# reembox.net
KiCad netlist of a schematic drawn in EAGLE
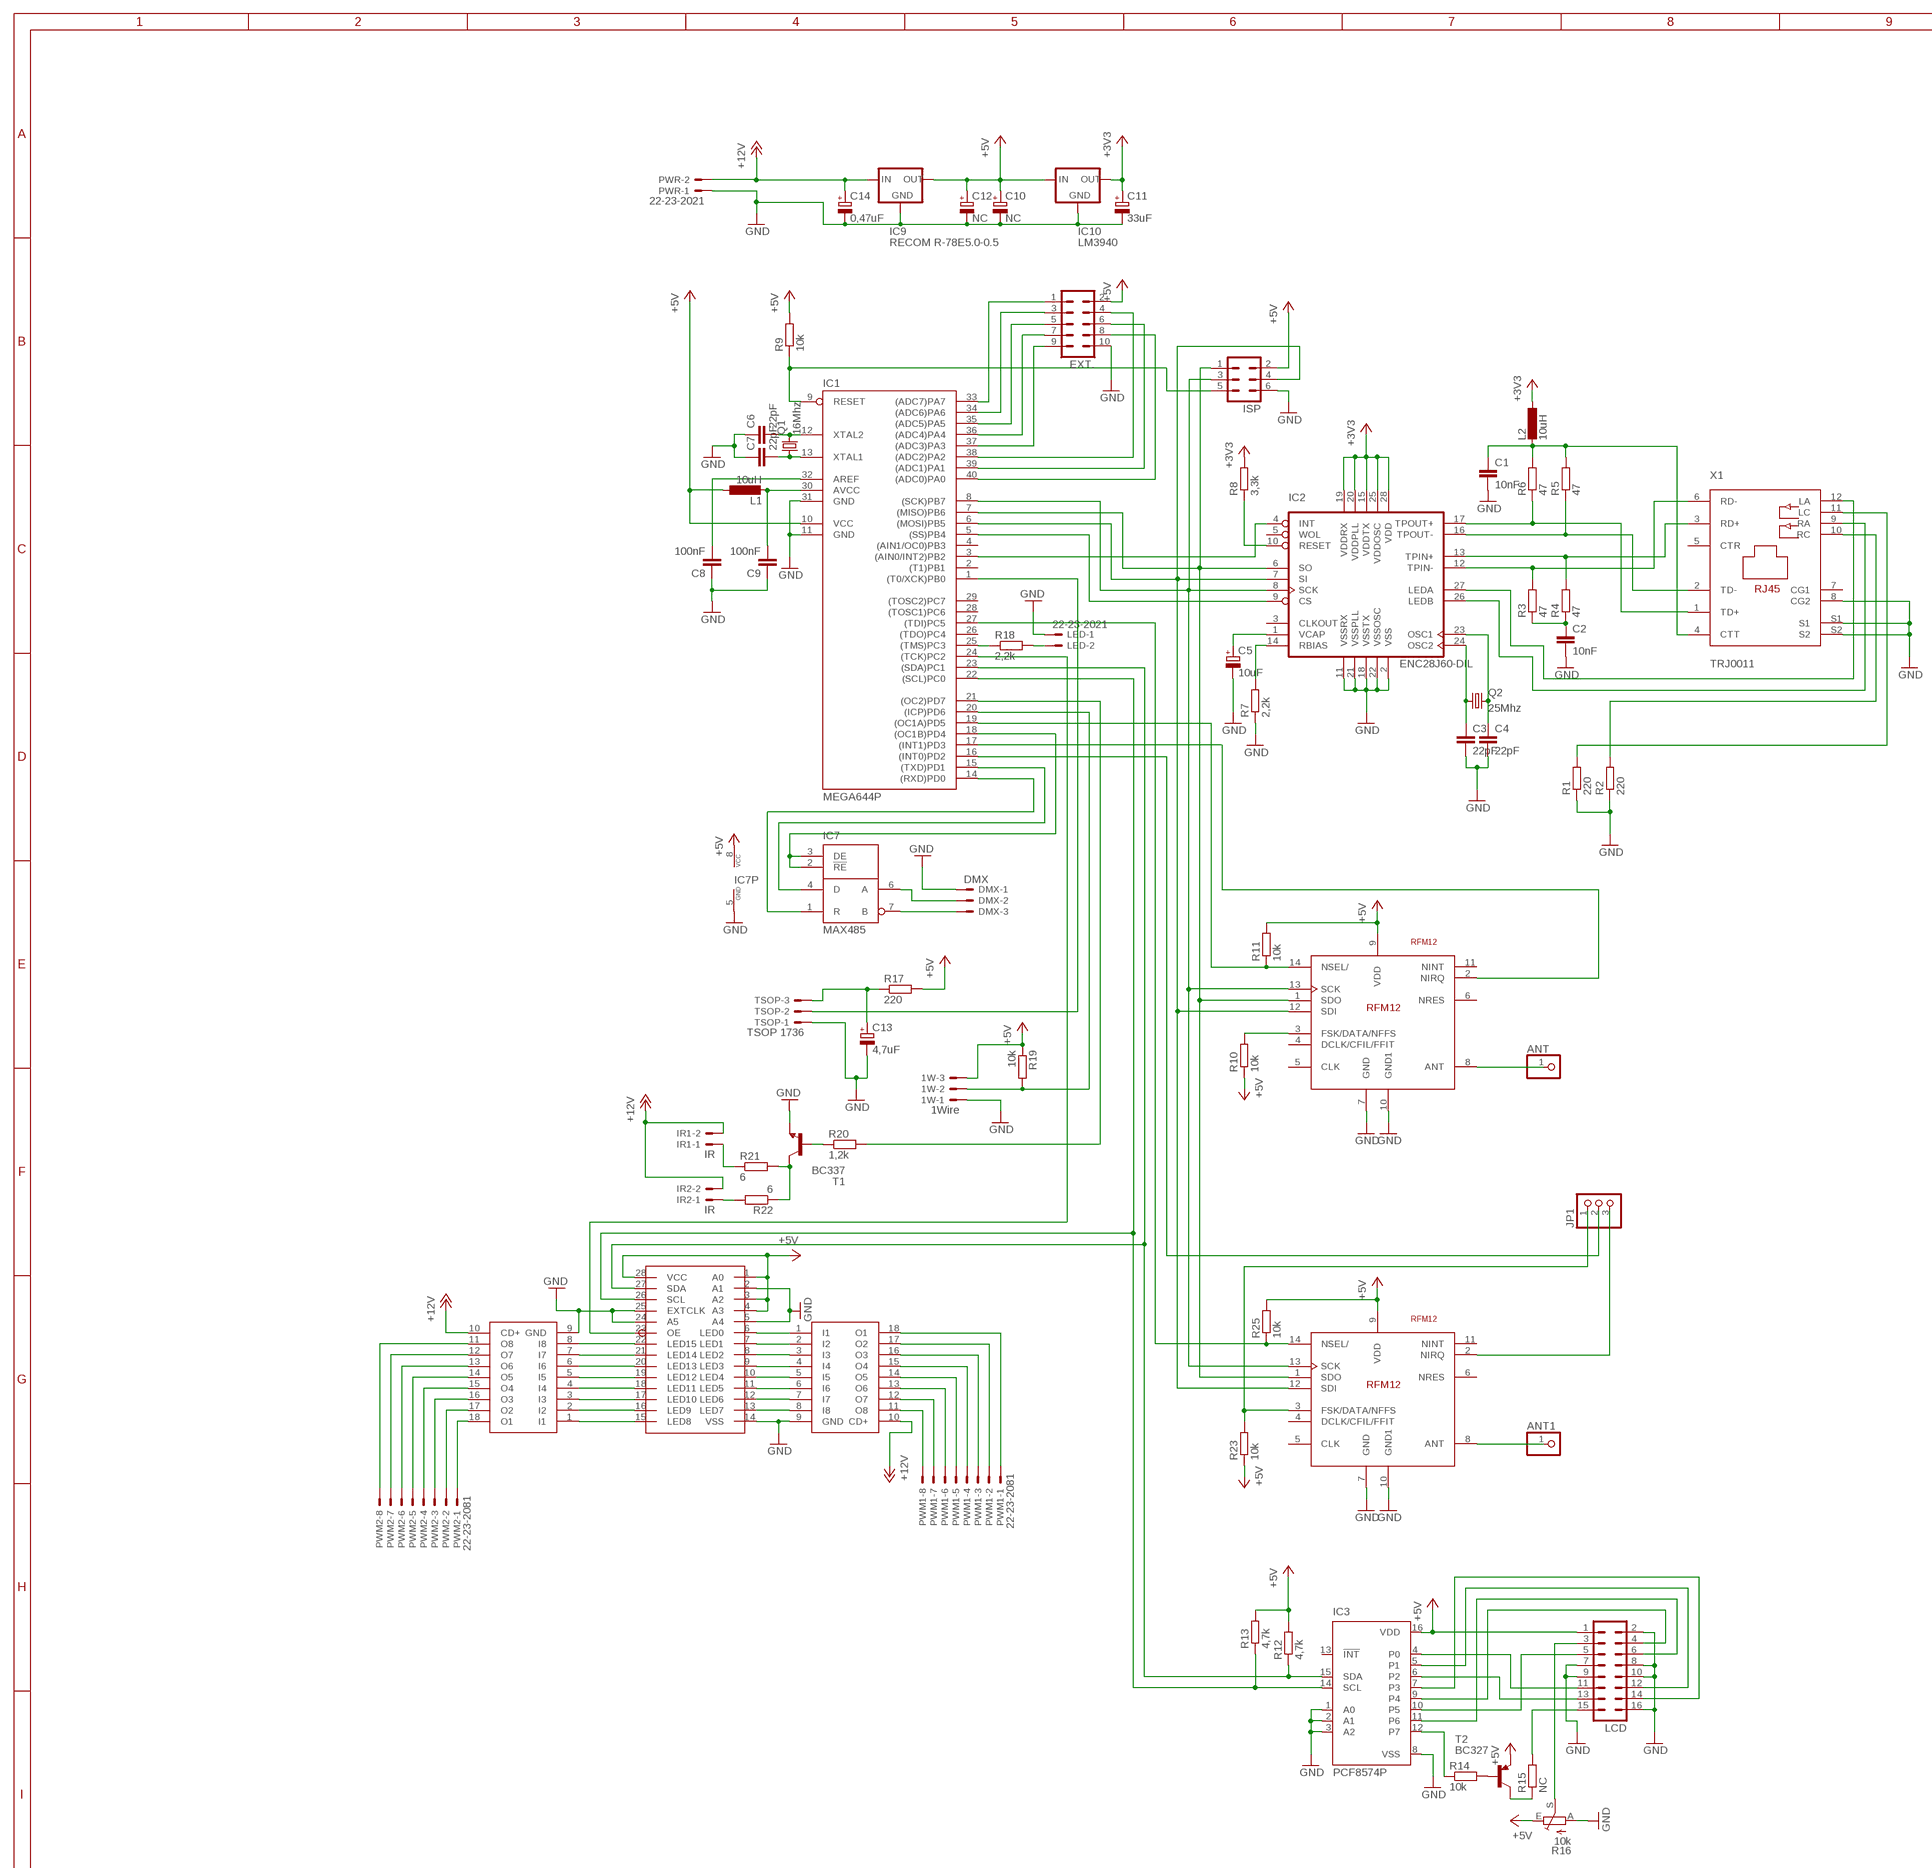
[diagram p0: schematic, sheet 1, part 1 of 2]
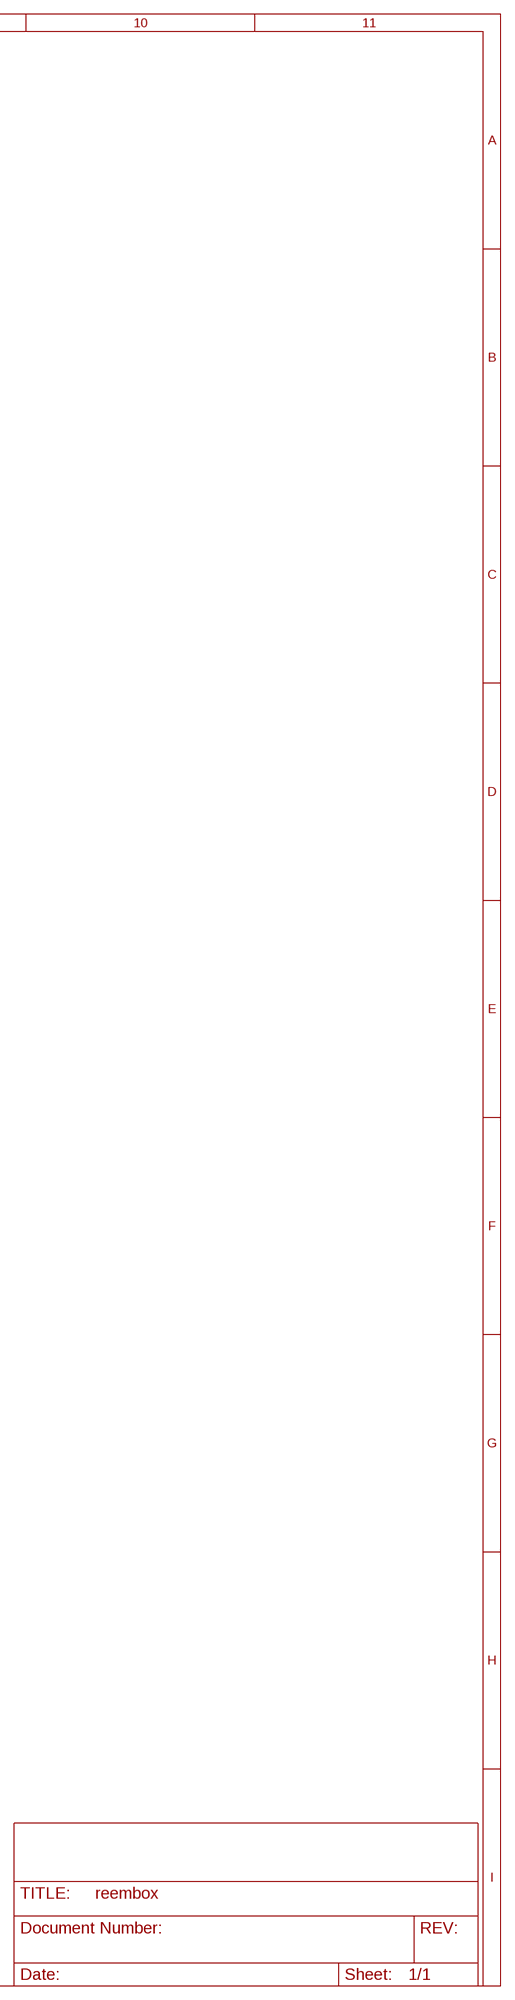
[diagram p1: schematic, sheet 1, part 2 of 2]

(export (version "E")
  (design (tool "Eeschema 10.0.6"))
  (components
    (comp (ref "1W")
      (value "1Wire")
      (footprint "eagle-import:CON-MOLEX_22-23-2031")
      (fields (field (name "MF") "MOLEX") (field (name "MPN") "22-23-2031"))
      (libsource (lib "eagle-import") (part "CON-MOLEX_22-23-2031"))
    )
    (comp (ref "ANT")
      (value "PINHD-1X1")
      (footprint "eagle-import:1X01")
      (libsource (lib "eagle-import") (part "PINHD-1X1"))
    )
    (comp (ref "ANT1")
      (value "PINHD-1X1")
      (footprint "eagle-import:1X01")
      (libsource (lib "eagle-import") (part "PINHD-1X1"))
    )
    (comp (ref "C1")
      (value "10nF")
      (footprint "eagle-import:C050-025X075")
      (libsource (lib "eagle-import") (part "C-EU050-025X075"))
    )
    (comp (ref "C2")
      (value "10nF")
      (footprint "eagle-import:C050-025X075")
      (libsource (lib "eagle-import") (part "C-EU050-025X075"))
    )
    (comp (ref "C3")
      (value "22pF")
      (footprint "eagle-import:C050-024X044")
      (libsource (lib "eagle-import") (part "C-EU050-024X044"))
    )
    (comp (ref "C4")
      (value "22pF")
      (footprint "eagle-import:C050-024X044")
      (libsource (lib "eagle-import") (part "C-EU050-024X044"))
    )
    (comp (ref "C5")
      (value "10uF")
      (footprint "eagle-import:E2,5-6")
      (libsource (lib "eagle-import") (part "CPOL-EUE2.5-6"))
    )
    (comp (ref "C6")
      (value "22pF")
      (footprint "eagle-import:C050-024X044")
      (libsource (lib "eagle-import") (part "C-EU050-024X044"))
    )
    (comp (ref "C7")
      (value "22pF")
      (footprint "eagle-import:C050-024X044")
      (libsource (lib "eagle-import") (part "C-EU050-024X044"))
    )
    (comp (ref "C8")
      (value "100nF")
      (footprint "eagle-import:C050-025X075")
      (libsource (lib "eagle-import") (part "C-EU050-025X075"))
    )
    (comp (ref "C9")
      (value "100nF")
      (footprint "eagle-import:C050-025X075")
      (libsource (lib "eagle-import") (part "C-EU050-025X075"))
    )
    (comp (ref "C10")
      (value "NC")
      (footprint "eagle-import:E2,5-6")
      (libsource (lib "eagle-import") (part "CPOL-EUE2.5-6"))
    )
    (comp (ref "C11")
      (value "33uF")
      (footprint "eagle-import:E2,5-6")
      (libsource (lib "eagle-import") (part "CPOL-EUE2.5-6"))
    )
    (comp (ref "C12")
      (value "NC")
      (footprint "eagle-import:E2,5-6")
      (libsource (lib "eagle-import") (part "CPOL-EUE2.5-6"))
    )
    (comp (ref "C13")
      (value "4,7uF")
      (footprint "eagle-import:E2,5-6E")
      (libsource (lib "eagle-import") (part "CPOL-EUE2,5-6E"))
    )
    (comp (ref "C14")
      (value "0,47uF")
      (footprint "eagle-import:E2,5-6")
      (libsource (lib "eagle-import") (part "CPOL-EUE2.5-6"))
    )
    (comp (ref "DMX")
      (value "DMX")
      (footprint "eagle-import:22-23-2031")
      (fields (field (name "MF") "MOLEX") (field (name "MPN") "22-23-2031"))
      (libsource (lib "eagle-import") (part "22-23-2031"))
    )
    (comp (ref "EXT.")
      (value "ML10L")
      (footprint "eagle-import:ML10L")
      (fields (field (name "OC_FARNELL") "unknown") (field (name "OC_NEWARK") "unknown"))
      (libsource (lib "eagle-import") (part "ML10L"))
    )
    (comp (ref "IC1")
      (value "MEGA644P")
      (footprint "eagle-import:DIL40")
      (fields (field (name "MPN") "ATMEGA32-16PU"))
      (libsource (lib "eagle-import") (part "MEGA32-P"))
    )
    (comp (ref "IC2")
      (value "ENC28J60-DIL")
      (footprint "eagle-import:DIL28-3")
      (libsource (lib "eagle-import") (part "ENC28J60-DIL"))
    )
    (comp (ref "IC3")
      (value "PCF8574P")
      (footprint "eagle-import:DIL16")
      (fields (field (name "MPN") "PCF8574PN"))
      (libsource (lib "eagle-import") (part "PCF8574P"))
    )
    (comp (ref "IC4")
      (value "PCA9685PW")
      (footprint "eagle-import:TSSOP28")
      (libsource (lib "eagle-import") (part "PCA9685PW"))
    )
    (comp (ref "IC5")
      (value "ULN2803")
      (footprint "eagle-import:DIL18")
      (libsource (lib "eagle-import") (part "ULN2803"))
    )
    (comp (ref "IC6")
      (value "ULN2803")
      (footprint "eagle-import:DIL18")
      (libsource (lib "eagle-import") (part "ULN2803"))
    )
    (comp (ref "IC7")
      (value "MAX485")
      (footprint "eagle-import:DIL08")
      (fields (field (name "MF") "TEXAS INSTRUMENTS") (field (name "MPN") "SN75ALS176P"))
      (libsource (lib "eagle-import") (part "75ALS176P"))
    )
    (comp (ref "IC8")
      (value "RFM12")
      (footprint "eagle-import:RFM12")
      (libsource (lib "eagle-import") (part "FRM12"))
    )
    (comp (ref "IC9")
      (value "RECOM R-78E5.0-0.5")
      (footprint "eagle-import:78XXS")
      (libsource (lib "eagle-import") (part "78XXS"))
    )
    (comp (ref "IC10")
      (value "LM3940")
      (footprint "eagle-import:78XXS")
      (libsource (lib "eagle-import") (part "78XXS"))
    )
    (comp (ref "IC11")
      (value "RFM12")
      (footprint "eagle-import:RFM12")
      (libsource (lib "eagle-import") (part "FRM12"))
    )
    (comp (ref "IR1")
      (value "IR")
      (footprint "eagle-import:22-23-2021")
      (fields (field (name "MF") "MOLEX") (field (name "MPN") "22-23-2021"))
      (libsource (lib "eagle-import") (part "22-23-2021"))
    )
    (comp (ref "IR2")
      (value "IR")
      (footprint "eagle-import:22-23-2021")
      (fields
        (field (name "MF") "MOLEX")
        (field (name "MPN") "22-23-2021")
        (field (name "MF_1") "MOLEX")
        (field (name "MPN_1") "22-23-2021")
        (field (name "OC_FARNELL") "1462926")
        (field (name "OC_NEWARK") "25C3832")
      )
      (libsource (lib "eagle-import") (part "22-23-2021"))
    )
    (comp (ref "ISP")
      (value "ML6")
      (footprint "eagle-import:ML6")
      (libsource (lib "eagle-import") (part "ML6"))
    )
    (comp (ref "JP1")
      (value "PINHD-1X3")
      (footprint "eagle-import:1X03")
      (libsource (lib "eagle-import") (part "PINHD-1X3"))
    )
    (comp (ref "L1")
      (value "10uH")
      (footprint "eagle-import:0207_2V")
      (libsource (lib "eagle-import") (part "L-EU0207/2V"))
    )
    (comp (ref "L2")
      (value "10uH")
      (footprint "eagle-import:0207_2V")
      (libsource (lib "eagle-import") (part "L-EU0207/2V"))
    )
    (comp (ref "LCD")
      (value "ML16")
      (footprint "eagle-import:ML16")
      (libsource (lib "eagle-import") (part "ML16"))
    )
    (comp (ref "LED")
      (value "22-23-2021")
      (footprint "eagle-import:22-23-2021")
      (fields
        (field (name "MF") "MOLEX")
        (field (name "MF_1") "MOLEX")
        (field (name "MPN") "22-23-2021")
        (field (name "OC_FARNELL") "1462926")
        (field (name "OC_NEWARK") "25C3832")
      )
      (libsource (lib "eagle-import") (part "22-23-2021"))
    )
    (comp (ref "PWM1")
      (value "22-23-2081")
      (footprint "eagle-import:22-23-2081")
      (fields (field (name "MF") "MOLEX"))
      (libsource (lib "eagle-import") (part "22-23-2081"))
    )
    (comp (ref "PWM2")
      (value "22-23-2081")
      (footprint "eagle-import:22-23-2081")
      (fields (field (name "MF") "MOLEX"))
      (libsource (lib "eagle-import") (part "22-23-2081"))
    )
    (comp (ref "PWR")
      (value "22-23-2021")
      (footprint "eagle-import:22-23-2021")
      (fields (field (name "MF") "MOLEX"))
      (libsource (lib "eagle-import") (part "22-23-2021"))
    )
    (comp (ref "Q1")
      (value "16Mhz")
      (footprint "eagle-import:HC49U-V")
      (libsource (lib "eagle-import") (part "CRYSTALHC49U-V"))
    )
    (comp (ref "Q2")
      (value "25Mhz")
      (footprint "eagle-import:HC49U-V")
      (libsource (lib "eagle-import") (part "CRYSTALHC49U-V"))
    )
    (comp (ref "R1")
      (value "220")
      (footprint "eagle-import:0207_2V")
      (libsource (lib "eagle-import") (part "R-EU_0207/2V"))
    )
    (comp (ref "R2")
      (value "220")
      (footprint "eagle-import:0207_2V")
      (libsource (lib "eagle-import") (part "R-EU_0207/2V"))
    )
    (comp (ref "R3")
      (value "47")
      (footprint "eagle-import:0207_2V")
      (libsource (lib "eagle-import") (part "R-EU_0207/2V"))
    )
    (comp (ref "R4")
      (value "47")
      (footprint "eagle-import:0207_2V")
      (libsource (lib "eagle-import") (part "R-EU_0207/2V"))
    )
    (comp (ref "R5")
      (value "47")
      (footprint "eagle-import:0207_2V")
      (libsource (lib "eagle-import") (part "R-EU_0207/2V"))
    )
    (comp (ref "R6")
      (value "47")
      (footprint "eagle-import:0207_2V")
      (libsource (lib "eagle-import") (part "R-EU_0207/2V"))
    )
    (comp (ref "R7")
      (value "2,2k")
      (footprint "eagle-import:0207_7")
      (libsource (lib "eagle-import") (part "resistor_R-EU_0207/7"))
    )
    (comp (ref "R8")
      (value "3,3k")
      (footprint "eagle-import:0207_10")
      (libsource (lib "eagle-import") (part "R-EU_0207/10"))
    )
    (comp (ref "R9")
      (value "10k")
      (footprint "eagle-import:0207_2V")
      (libsource (lib "eagle-import") (part "R-EU_0207/2V"))
    )
    (comp (ref "R10")
      (value "10k")
      (footprint "eagle-import:0207_10")
      (libsource (lib "eagle-import") (part "R-EU_0207/10"))
    )
    (comp (ref "R11")
      (value "10k")
      (footprint "eagle-import:0207_10")
      (libsource (lib "eagle-import") (part "R-EU_0207/10"))
    )
    (comp (ref "R12")
      (value "4,7k")
      (footprint "eagle-import:0207_10")
      (libsource (lib "eagle-import") (part "R-EU_0207/10"))
    )
    (comp (ref "R13")
      (value "4,7k")
      (footprint "eagle-import:0207_10")
      (libsource (lib "eagle-import") (part "R-EU_0207/10"))
    )
    (comp (ref "R14")
      (value "10k")
      (footprint "eagle-import:0207_10")
      (libsource (lib "eagle-import") (part "R-EU_0207/10"))
    )
    (comp (ref "R15")
      (value "NC")
      (footprint "eagle-import:0207_10")
      (libsource (lib "eagle-import") (part "R-EU_0207/10"))
    )
    (comp (ref "R16")
      (value "10k")
      (footprint "eagle-import:PT-10S")
      (libsource (lib "eagle-import") (part "TRIM_EU-PT10S"))
    )
    (comp (ref "R17")
      (value "220")
      (footprint "eagle-import:0207_2V")
      (libsource (lib "eagle-import") (part "R-EU_0207/2V"))
    )
    (comp (ref "R18")
      (value "2,2k")
      (footprint "eagle-import:0207_2V")
      (libsource (lib "eagle-import") (part "R-EU_0207/2V"))
    )
    (comp (ref "R19")
      (value "10k")
      (footprint "eagle-import:0207_10")
      (libsource (lib "eagle-import") (part "R-EU_0207/10"))
    )
    (comp (ref "R20")
      (value "1,2k")
      (footprint "eagle-import:RCL_0207_2V")
      (libsource (lib "eagle-import") (part "RCL_R-EU_0207/2V"))
    )
    (comp (ref "R21")
      (value "6")
      (footprint "eagle-import:RCL_0207_2V")
      (libsource (lib "eagle-import") (part "RCL_R-EU_0207/2V"))
    )
    (comp (ref "R22")
      (value "6")
      (footprint "eagle-import:RCL_0207_2V")
      (libsource (lib "eagle-import") (part "RCL_R-EU_0207/2V"))
    )
    (comp (ref "R23")
      (value "10k")
      (footprint "eagle-import:0207_10")
      (libsource (lib "eagle-import") (part "R-EU_0207/10"))
    )
    (comp (ref "R25")
      (value "10k")
      (footprint "eagle-import:0207_2V")
      (libsource (lib "eagle-import") (part "R-EU_0207/2V"))
    )
    (comp (ref "T1")
      (value "BC337")
      (footprint "eagle-import:TO92")
      (libsource (lib "eagle-import") (part "BC337"))
    )
    (comp (ref "T2")
      (value "BC327")
      (footprint "eagle-import:TO92")
      (libsource (lib "eagle-import") (part "BC327"))
    )
    (comp (ref "TSOP")
      (value "TSOP 1736")
      (footprint "eagle-import:22-23-2031")
      (fields (field (name "MF") "MOLEX") (field (name "MPN") "22-23-2031"))
      (libsource (lib "eagle-import") (part "22-23-2031"))
    )
    (comp (ref "X1")
      (value "TRJ0011")
      (footprint "eagle-import:TRJ0011")
      (libsource (lib "eagle-import") (part "TRJ0011"))
    )
  )
  (nets
    (net (code "1") (name "+3V3") (class "Default")
      (node (ref "C11") (pin "+") (pinfunction "+_+") (pintype "passive"))
      (node (ref "IC10") (pin "OUT") (pinfunction "OUT_OUT") (pintype "passive"))
      (node (ref "IC2") (pin "15") (pinfunction "VDDTX_15") (pintype "power_in"))
      (node (ref "IC2") (pin "19") (pinfunction "VDDRX_19") (pintype "power_in"))
      (node (ref "IC2") (pin "20") (pinfunction "VDDPLL_20") (pintype "power_in"))
      (node (ref "IC2") (pin "25") (pinfunction "VDDOSC_25") (pintype "power_in"))
      (node (ref "IC2") (pin "28") (pinfunction "VDD_28") (pintype "power_in"))
      (node (ref "L2") (pin "1") (pinfunction "1_1") (pintype "passive"))
      (node (ref "R8") (pin "2") (pinfunction "2_2") (pintype "passive"))
    )
    (net (code "2") (name "+5V") (class "Default")
      (node (ref "1W") (pin "3") (pinfunction "S_3") (pintype "passive"))
      (node (ref "C10") (pin "+") (pinfunction "+_+") (pintype "passive"))
      (node (ref "C12") (pin "+") (pinfunction "+_+") (pintype "passive"))
      (node (ref "EXT.") (pin "2") (pinfunction "2_2") (pintype "passive"))
      (node (ref "IC1") (pin "10") (pinfunction "VCC_10") (pintype "power_in"))
      (node (ref "IC10") (pin "IN") (pinfunction "IN_IN") (pintype "input"))
      (node (ref "IC11") (pin "9") (pinfunction "VDD_9") (pintype "power_in"))
      (node (ref "IC3") (pin "16") (pinfunction "VDD_16") (pintype "power_in"))
      (node (ref "IC4") (pin "1") (pinfunction "A0_1") (pintype "bidirectional"))
      (node (ref "IC4") (pin "28") (pinfunction "VCC_28") (pintype "bidirectional"))
      (node (ref "IC4") (pin "3") (pinfunction "A2_3") (pintype "bidirectional"))
      (node (ref "IC4") (pin "4") (pinfunction "A3_4") (pintype "bidirectional"))
      (node (ref "IC7") (pin "8") (pinfunction "VCC_8") (pintype "power_in"))
      (node (ref "IC8") (pin "9") (pinfunction "VDD_9") (pintype "power_in"))
      (node (ref "IC9") (pin "OUT") (pinfunction "OUT_OUT") (pintype "passive"))
      (node (ref "ISP") (pin "2") (pinfunction "2_2") (pintype "passive"))
      (node (ref "L1") (pin "1") (pinfunction "1_1") (pintype "passive"))
      (node (ref "LCD") (pin "1") (pinfunction "1_1") (pintype "passive"))
      (node (ref "R10") (pin "1") (pinfunction "1_1") (pintype "passive"))
      (node (ref "R11") (pin "2") (pinfunction "2_2") (pintype "passive"))
      (node (ref "R12") (pin "2") (pinfunction "2_2") (pintype "passive"))
      (node (ref "R13") (pin "2") (pinfunction "2_2") (pintype "passive"))
      (node (ref "R16") (pin "E") (pinfunction "E_E") (pintype "passive"))
      (node (ref "R17") (pin "2") (pinfunction "2_2") (pintype "passive"))
      (node (ref "R19") (pin "1") (pinfunction "1_1") (pintype "passive"))
      (node (ref "R23") (pin "1") (pinfunction "1_1") (pintype "passive"))
      (node (ref "R25") (pin "2") (pinfunction "2_2") (pintype "passive"))
      (node (ref "R9") (pin "2") (pinfunction "2_2") (pintype "passive"))
      (node (ref "T2") (pin "1") (pinfunction "E_1") (pintype "passive"))
    )
    (net (code "3") (name "+12V") (class "Default")
      (node (ref "C14") (pin "+") (pinfunction "+_+") (pintype "passive"))
      (node (ref "IC5") (pin "10") (pinfunction "CD+_10") (pintype "bidirectional"))
      (node (ref "IC6") (pin "10") (pinfunction "CD+_10") (pintype "bidirectional"))
      (node (ref "IC9") (pin "IN") (pinfunction "IN_IN") (pintype "input"))
      (node (ref "IR1") (pin "2") (pinfunction "S_2") (pintype "passive"))
      (node (ref "IR2") (pin "2") (pinfunction "S_2") (pintype "passive"))
      (node (ref "PWR") (pin "2") (pinfunction "S_2") (pintype "passive"))
    )
    (net (code "4") (name "GND") (class "Default")
      (node (ref "1W") (pin "1") (pinfunction "S_1") (pintype "passive"))
      (node (ref "C1") (pin "2") (pinfunction "2_2") (pintype "passive"))
      (node (ref "C10") (pin "-") (pinfunction "-_-") (pintype "passive"))
      (node (ref "C11") (pin "-") (pinfunction "-_-") (pintype "passive"))
      (node (ref "C12") (pin "-") (pinfunction "-_-") (pintype "passive"))
      (node (ref "C13") (pin "-") (pinfunction "-_-") (pintype "passive"))
      (node (ref "C14") (pin "-") (pinfunction "-_-") (pintype "passive"))
      (node (ref "C2") (pin "2") (pinfunction "2_2") (pintype "passive"))
      (node (ref "C3") (pin "2") (pinfunction "2_2") (pintype "passive"))
      (node (ref "C4") (pin "2") (pinfunction "2_2") (pintype "passive"))
      (node (ref "C5") (pin "-") (pinfunction "-_-") (pintype "passive"))
      (node (ref "C6") (pin "1") (pinfunction "1_1") (pintype "passive"))
      (node (ref "C7") (pin "1") (pinfunction "1_1") (pintype "passive"))
      (node (ref "C8") (pin "1") (pinfunction "1_1") (pintype "passive"))
      (node (ref "C9") (pin "1") (pinfunction "1_1") (pintype "passive"))
      (node (ref "DMX") (pin "1") (pinfunction "S_1") (pintype "passive"))
      (node (ref "EXT.") (pin "10") (pinfunction "10_10") (pintype "passive"))
      (node (ref "IC1") (pin "11") (pinfunction "GND_11") (pintype "power_in"))
      (node (ref "IC1") (pin "31") (pinfunction "GND_31") (pintype "power_in"))
      (node (ref "IC10") (pin "GND") (pinfunction "GND_GND") (pintype "input"))
      (node (ref "IC11") (pin "10") (pinfunction "GND1_10") (pintype "passive"))
      (node (ref "IC11") (pin "7") (pinfunction "GND_7") (pintype "passive"))
      (node (ref "IC2") (pin "11") (pinfunction "VSSRX_11") (pintype "power_in"))
      (node (ref "IC2") (pin "18") (pinfunction "VSSTX_18") (pintype "power_in"))
      (node (ref "IC2") (pin "2") (pinfunction "VSS_2") (pintype "power_in"))
      (node (ref "IC2") (pin "21") (pinfunction "VSSPLL_21") (pintype "power_in"))
      (node (ref "IC2") (pin "22") (pinfunction "VSSOSC_22") (pintype "power_in"))
      (node (ref "IC3") (pin "1") (pinfunction "A0_1") (pintype "input"))
      (node (ref "IC3") (pin "2") (pinfunction "A1_2") (pintype "input"))
      (node (ref "IC3") (pin "3") (pinfunction "A2_3") (pintype "input"))
      (node (ref "IC3") (pin "8") (pinfunction "VSS_8") (pintype "power_in"))
      (node (ref "IC4") (pin "14") (pinfunction "VSS_14") (pintype "bidirectional"))
      (node (ref "IC4") (pin "2") (pinfunction "A1_2") (pintype "bidirectional"))
      (node (ref "IC4") (pin "24") (pinfunction "A5_24") (pintype "bidirectional"))
      (node (ref "IC4") (pin "25") (pinfunction "EXTCLK_25") (pintype "bidirectional"))
      (node (ref "IC4") (pin "5") (pinfunction "A4_5") (pintype "bidirectional"))
      (node (ref "IC5") (pin "9") (pinfunction "GND_9") (pintype "bidirectional"))
      (node (ref "IC6") (pin "9") (pinfunction "GND_9") (pintype "bidirectional"))
      (node (ref "IC7") (pin "5") (pinfunction "GND_5") (pintype "power_in"))
      (node (ref "IC8") (pin "10") (pinfunction "GND1_10") (pintype "passive"))
      (node (ref "IC8") (pin "7") (pinfunction "GND_7") (pintype "passive"))
      (node (ref "IC9") (pin "GND") (pinfunction "GND_GND") (pintype "input"))
      (node (ref "ISP") (pin "6") (pinfunction "6_6") (pintype "passive"))
      (node (ref "LCD") (pin "10") (pinfunction "10_10") (pintype "passive"))
      (node (ref "LCD") (pin "16") (pinfunction "16_16") (pintype "passive"))
      (node (ref "LCD") (pin "2") (pinfunction "2_2") (pintype "passive"))
      (node (ref "LCD") (pin "7") (pinfunction "7_7") (pintype "passive"))
      (node (ref "LCD") (pin "8") (pinfunction "8_8") (pintype "passive"))
      (node (ref "LCD") (pin "9") (pinfunction "9_9") (pintype "passive"))
      (node (ref "LED") (pin "1") (pinfunction "S_1") (pintype "passive"))
      (node (ref "PWR") (pin "1") (pinfunction "S_1") (pintype "passive"))
      (node (ref "R1") (pin "1") (pinfunction "1_1") (pintype "passive"))
      (node (ref "R16") (pin "A") (pinfunction "A_A") (pintype "passive"))
      (node (ref "R2") (pin "1") (pinfunction "1_1") (pintype "passive"))
      (node (ref "R7") (pin "1") (pinfunction "1_1") (pintype "passive"))
      (node (ref "T1") (pin "1") (pinfunction "E_1") (pintype "passive"))
      (node (ref "TSOP") (pin "1") (pinfunction "S_1") (pintype "passive"))
      (node (ref "X1") (pin "8") (pinfunction "CG2_8") (pintype "passive"))
      (node (ref "X1") (pin "S1") (pinfunction "S1_S1") (pintype "passive"))
      (node (ref "X1") (pin "S2") (pinfunction "S2_S2") (pintype "passive"))
    )
    (net (code "5") (name "Net-(1WB-S)") (class "Default")
      (node (ref "1W") (pin "2") (pinfunction "S_2") (pintype "passive"))
      (node (ref "IC1") (pin "20") (pinfunction "(ICP)PD6_20") (pintype "bidirectional"))
      (node (ref "R19") (pin "2") (pinfunction "2_2") (pintype "passive"))
    )
    (net (code "6") (name "Net-(C2-Pad1)") (class "Default")
      (node (ref "C2") (pin "1") (pinfunction "1_1") (pintype "passive"))
      (node (ref "R3") (pin "1") (pinfunction "1_1") (pintype "passive"))
      (node (ref "R4") (pin "1") (pinfunction "1_1") (pintype "passive"))
    )
    (net (code "7") (name "Net-(DMXB-S)") (class "Default")
      (node (ref "DMX") (pin "2") (pinfunction "S_2") (pintype "passive"))
      (node (ref "IC7") (pin "6") (pinfunction "A_6") (pintype "bidirectional"))
    )
    (net (code "8") (name "Net-(DMXC-S)") (class "Default")
      (node (ref "DMX") (pin "3") (pinfunction "S_3") (pintype "passive"))
      (node (ref "IC7") (pin "7") (pinfunction "B_7") (pintype "bidirectional"))
    )
    (net (code "9") (name "Net-(IC1-(ADC0)PA0)") (class "Default")
      (node (ref "EXT.") (pin "8") (pinfunction "8_8") (pintype "passive"))
      (node (ref "IC1") (pin "40") (pinfunction "(ADC0)PA0_40") (pintype "bidirectional"))
    )
    (net (code "10") (name "Net-(IC1-(ADC1)PA1)") (class "Default")
      (node (ref "EXT.") (pin "6") (pinfunction "6_6") (pintype "passive"))
      (node (ref "IC1") (pin "39") (pinfunction "(ADC1)PA1_39") (pintype "bidirectional"))
    )
    (net (code "11") (name "Net-(IC1-(ADC2)PA2)") (class "Default")
      (node (ref "EXT.") (pin "4") (pinfunction "4_4") (pintype "passive"))
      (node (ref "IC1") (pin "38") (pinfunction "(ADC2)PA2_38") (pintype "bidirectional"))
    )
    (net (code "12") (name "Net-(IC1-(ADC3)PA3)") (class "Default")
      (node (ref "EXT.") (pin "9") (pinfunction "9_9") (pintype "passive"))
      (node (ref "IC1") (pin "37") (pinfunction "(ADC3)PA3_37") (pintype "bidirectional"))
    )
    (net (code "13") (name "Net-(IC1-(ADC4)PA4)") (class "Default")
      (node (ref "EXT.") (pin "7") (pinfunction "7_7") (pintype "passive"))
      (node (ref "IC1") (pin "36") (pinfunction "(ADC4)PA4_36") (pintype "bidirectional"))
    )
    (net (code "14") (name "Net-(IC1-(ADC5)PA5)") (class "Default")
      (node (ref "EXT.") (pin "5") (pinfunction "5_5") (pintype "passive"))
      (node (ref "IC1") (pin "35") (pinfunction "(ADC5)PA5_35") (pintype "bidirectional"))
    )
    (net (code "15") (name "Net-(IC1-(ADC6)PA6)") (class "Default")
      (node (ref "EXT.") (pin "3") (pinfunction "3_3") (pintype "passive"))
      (node (ref "IC1") (pin "34") (pinfunction "(ADC6)PA6_34") (pintype "bidirectional"))
    )
    (net (code "16") (name "Net-(IC1-(ADC7)PA7)") (class "Default")
      (node (ref "EXT.") (pin "1") (pinfunction "1_1") (pintype "passive"))
      (node (ref "IC1") (pin "33") (pinfunction "(ADC7)PA7_33") (pintype "bidirectional"))
    )
    (net (code "17") (name "Net-(IC1-(AIN0{slash}INT2)PB2)") (class "Default")
      (node (ref "IC1") (pin "3") (pinfunction "(AIN0/INT2)PB2_3") (pintype "bidirectional"))
      (node (ref "IC2") (pin "4") (pinfunction "INT_4") (pintype "output"))
    )
    (net (code "18") (name "Net-(IC1-(INT0)PD2)") (class "Default")
      (node (ref "IC1") (pin "16") (pinfunction "(INT0)PD2_16") (pintype "bidirectional"))
      (node (ref "JP1") (pin "2") (pinfunction "2_2") (pintype "passive"))
    )
    (net (code "19") (name "Net-(IC1-(INT1)PD3)") (class "Default")
      (node (ref "IC1") (pin "17") (pinfunction "(INT1)PD3_17") (pintype "bidirectional"))
      (node (ref "IC8") (pin "2") (pinfunction "NIRQ_2") (pintype "output"))
    )
    (net (code "20") (name "Net-(IC1-(MISO)PB6)") (class "Default")
      (node (ref "IC1") (pin "7") (pinfunction "(MISO)PB6_7") (pintype "bidirectional"))
      (node (ref "IC11") (pin "1") (pinfunction "SDO_1") (pintype "output"))
      (node (ref "IC2") (pin "6") (pinfunction "SO_6") (pintype "open_collector"))
      (node (ref "IC8") (pin "1") (pinfunction "SDO_1") (pintype "output"))
      (node (ref "ISP") (pin "1") (pinfunction "1_1") (pintype "passive"))
    )
    (net (code "21") (name "Net-(IC1-(MOSI)PB5)") (class "Default")
      (node (ref "IC1") (pin "6") (pinfunction "(MOSI)PB5_6") (pintype "bidirectional"))
      (node (ref "IC11") (pin "12") (pinfunction "SDI_12") (pintype "input"))
      (node (ref "IC2") (pin "7") (pinfunction "SI_7") (pintype "input"))
      (node (ref "IC8") (pin "12") (pinfunction "SDI_12") (pintype "input"))
      (node (ref "ISP") (pin "4") (pinfunction "4_4") (pintype "passive"))
    )
    (net (code "22") (name "Net-(IC1-(OC1A)PD5)") (class "Default")
      (node (ref "IC1") (pin "19") (pinfunction "(OC1A)PD5_19") (pintype "bidirectional"))
      (node (ref "IC8") (pin "14") (pinfunction "NSEL/_14") (pintype "input"))
      (node (ref "R11") (pin "1") (pinfunction "1_1") (pintype "passive"))
    )
    (net (code "23") (name "Net-(IC1-(OC1B)PD4)") (class "Default")
      (node (ref "IC1") (pin "18") (pinfunction "(OC1B)PD4_18") (pintype "bidirectional"))
      (node (ref "IC7") (pin "2") (pinfunction "~{RE}_2") (pintype "input"))
      (node (ref "IC7") (pin "3") (pinfunction "DE_3") (pintype "input"))
    )
    (net (code "24") (name "Net-(IC1-(OC2)PD7)") (class "Default")
      (node (ref "IC1") (pin "21") (pinfunction "(OC2)PD7_21") (pintype "bidirectional"))
      (node (ref "R20") (pin "2") (pinfunction "2_2") (pintype "passive"))
    )
    (net (code "25") (name "Net-(IC1-(RXD)PD0)") (class "Default")
      (node (ref "IC1") (pin "14") (pinfunction "(RXD)PD0_14") (pintype "bidirectional"))
      (node (ref "IC7") (pin "1") (pinfunction "R_1") (pintype "output"))
    )
    (net (code "26") (name "Net-(IC1-(SCK)PB7)") (class "Default")
      (node (ref "IC1") (pin "8") (pinfunction "(SCK)PB7_8") (pintype "bidirectional"))
      (node (ref "IC11") (pin "13") (pinfunction "SCK_13") (pintype "input"))
      (node (ref "IC2") (pin "8") (pinfunction "SCK_8") (pintype "input"))
      (node (ref "IC8") (pin "13") (pinfunction "SCK_13") (pintype "input"))
      (node (ref "ISP") (pin "3") (pinfunction "3_3") (pintype "passive"))
    )
    (net (code "27") (name "Net-(IC1-(SCL)PC0)") (class "Default")
      (node (ref "IC1") (pin "22") (pinfunction "(SCL)PC0_22") (pintype "bidirectional"))
      (node (ref "IC3") (pin "14") (pinfunction "SCL_14") (pintype "input"))
      (node (ref "IC4") (pin "26") (pinfunction "SCL_26") (pintype "bidirectional"))
      (node (ref "R13") (pin "1") (pinfunction "1_1") (pintype "passive"))
    )
    (net (code "28") (name "Net-(IC1-(SDA)PC1)") (class "Default")
      (node (ref "IC1") (pin "23") (pinfunction "(SDA)PC1_23") (pintype "bidirectional"))
      (node (ref "IC3") (pin "15") (pinfunction "SDA_15") (pintype "bidirectional"))
      (node (ref "IC4") (pin "27") (pinfunction "SDA_27") (pintype "bidirectional"))
      (node (ref "R12") (pin "1") (pinfunction "1_1") (pintype "passive"))
    )
    (net (code "29") (name "Net-(IC1-(SS)PB4)") (class "Default")
      (node (ref "IC1") (pin "5") (pinfunction "(SS)PB4_5") (pintype "bidirectional"))
      (node (ref "IC2") (pin "9") (pinfunction "CS_9") (pintype "input"))
    )
    (net (code "30") (name "Net-(IC1-(T0{slash}XCK)PB0)") (class "Default")
      (node (ref "IC1") (pin "1") (pinfunction "(T0/XCK)PB0_1") (pintype "bidirectional"))
      (node (ref "TSOP") (pin "2") (pinfunction "S_2") (pintype "passive"))
    )
    (net (code "31") (name "Net-(IC1-(TCK)PC2)") (class "Default")
      (node (ref "IC1") (pin "24") (pinfunction "(TCK)PC2_24") (pintype "bidirectional"))
      (node (ref "IC4") (pin "23") (pinfunction "OE_23") (pintype "bidirectional"))
    )
    (net (code "32") (name "Net-(IC1-(TDI)PC5)") (class "Default")
      (node (ref "IC1") (pin "27") (pinfunction "(TDI)PC5_27") (pintype "bidirectional"))
      (node (ref "IC11") (pin "14") (pinfunction "NSEL/_14") (pintype "input"))
      (node (ref "R25") (pin "1") (pinfunction "1_1") (pintype "passive"))
    )
    (net (code "33") (name "Net-(IC1-(TMS)PC3)") (class "Default")
      (node (ref "IC1") (pin "25") (pinfunction "(TMS)PC3_25") (pintype "bidirectional"))
      (node (ref "R18") (pin "1") (pinfunction "1_1") (pintype "passive"))
    )
    (net (code "34") (name "Net-(IC1-(TXD)PD1)") (class "Default")
      (node (ref "IC1") (pin "15") (pinfunction "(TXD)PD1_15") (pintype "bidirectional"))
      (node (ref "IC7") (pin "4") (pinfunction "D_4") (pintype "input"))
    )
    (net (code "35") (name "Net-(IC1-AREF)") (class "Default")
      (node (ref "C8") (pin "2") (pinfunction "2_2") (pintype "passive"))
      (node (ref "IC1") (pin "32") (pinfunction "AREF_32") (pintype "passive"))
    )
    (net (code "36") (name "Net-(IC1-AVCC)") (class "Default")
      (node (ref "C9") (pin "2") (pinfunction "2_2") (pintype "passive"))
      (node (ref "IC1") (pin "30") (pinfunction "AVCC_30") (pintype "power_in"))
      (node (ref "L1") (pin "2") (pinfunction "2_2") (pintype "passive"))
    )
    (net (code "37") (name "Net-(IC1-RESET)") (class "Default")
      (node (ref "IC1") (pin "9") (pinfunction "RESET_9") (pintype "input"))
      (node (ref "ISP") (pin "5") (pinfunction "5_5") (pintype "passive"))
      (node (ref "R9") (pin "1") (pinfunction "1_1") (pintype "passive"))
    )
    (net (code "38") (name "Net-(IC1-XTAL1)") (class "Default")
      (node (ref "C7") (pin "2") (pinfunction "2_2") (pintype "passive"))
      (node (ref "IC1") (pin "13") (pinfunction "XTAL1_13") (pintype "bidirectional"))
      (node (ref "Q1") (pin "1") (pinfunction "1_1") (pintype "passive"))
    )
    (net (code "39") (name "Net-(IC1-XTAL2)") (class "Default")
      (node (ref "C6") (pin "2") (pinfunction "2_2") (pintype "passive"))
      (node (ref "IC1") (pin "12") (pinfunction "XTAL2_12") (pintype "bidirectional"))
      (node (ref "Q1") (pin "2") (pinfunction "2_2") (pintype "passive"))
    )
    (net (code "40") (name "Net-(IC2-LEDA)") (class "Default")
      (node (ref "IC2") (pin "27") (pinfunction "LEDA_27") (pintype "output"))
      (node (ref "X1") (pin "12") (pinfunction "LA_12") (pintype "passive"))
    )
    (net (code "41") (name "Net-(IC2-LEDB)") (class "Default")
      (node (ref "IC2") (pin "26") (pinfunction "LEDB_26") (pintype "output"))
      (node (ref "X1") (pin "9") (pinfunction "RA_9") (pintype "passive"))
    )
    (net (code "42") (name "Net-(IC2-OSC1)") (class "Default")
      (node (ref "C4") (pin "1") (pinfunction "1_1") (pintype "passive"))
      (node (ref "IC2") (pin "23") (pinfunction "OSC1_23") (pintype "input"))
      (node (ref "Q2") (pin "2") (pinfunction "2_2") (pintype "passive"))
    )
    (net (code "43") (name "Net-(IC2-OSC2)") (class "Default")
      (node (ref "C3") (pin "1") (pinfunction "1_1") (pintype "passive"))
      (node (ref "IC2") (pin "24") (pinfunction "OSC2_24") (pintype "output"))
      (node (ref "Q2") (pin "1") (pinfunction "1_1") (pintype "passive"))
    )
    (net (code "44") (name "Net-(IC2-RBIAS)") (class "Default")
      (node (ref "IC2") (pin "14") (pinfunction "RBIAS_14") (pintype "passive"))
      (node (ref "R7") (pin "2") (pinfunction "2_2") (pintype "passive"))
    )
    (net (code "45") (name "Net-(IC2-RESET)") (class "Default")
      (node (ref "IC2") (pin "10") (pinfunction "RESET_10") (pintype "input"))
      (node (ref "R8") (pin "1") (pinfunction "1_1") (pintype "passive"))
    )
    (net (code "46") (name "Net-(IC2-TPIN+)") (class "Default")
      (node (ref "IC2") (pin "13") (pinfunction "TPIN+_13") (pintype "input"))
      (node (ref "R4") (pin "2") (pinfunction "2_2") (pintype "passive"))
      (node (ref "X1") (pin "3") (pinfunction "RD+_3") (pintype "passive"))
    )
    (net (code "47") (name "Net-(IC2-TPIN-)") (class "Default")
      (node (ref "IC2") (pin "12") (pinfunction "TPIN-_12") (pintype "input"))
      (node (ref "R3") (pin "2") (pinfunction "2_2") (pintype "passive"))
      (node (ref "X1") (pin "6") (pinfunction "RD-_6") (pintype "passive"))
    )
    (net (code "48") (name "Net-(IC2-TPOUT+)") (class "Default")
      (node (ref "IC2") (pin "17") (pinfunction "TPOUT+_17") (pintype "output"))
      (node (ref "R6") (pin "1") (pinfunction "1_1") (pintype "passive"))
      (node (ref "X1") (pin "1") (pinfunction "TD+_1") (pintype "passive"))
    )
    (net (code "49") (name "Net-(IC2-TPOUT-)") (class "Default")
      (node (ref "IC2") (pin "16") (pinfunction "TPOUT-_16") (pintype "output"))
      (node (ref "R5") (pin "1") (pinfunction "1_1") (pintype "passive"))
      (node (ref "X1") (pin "2") (pinfunction "TD-_2") (pintype "passive"))
    )
    (net (code "50") (name "Net-(IC2-VCAP)") (class "Default")
      (node (ref "C5") (pin "+") (pinfunction "+_+") (pintype "passive"))
      (node (ref "IC2") (pin "1") (pinfunction "VCAP_1") (pintype "power_in"))
    )
    (net (code "51") (name "Net-(IC3-P0)") (class "Default")
      (node (ref "IC3") (pin "4") (pinfunction "P0_4") (pintype "bidirectional"))
      (node (ref "LCD") (pin "11") (pinfunction "11_11") (pintype "passive"))
    )
    (net (code "52") (name "Net-(IC3-P1)") (class "Default")
      (node (ref "IC3") (pin "5") (pinfunction "P1_5") (pintype "bidirectional"))
      (node (ref "LCD") (pin "12") (pinfunction "12_12") (pintype "passive"))
    )
    (net (code "53") (name "Net-(IC3-P2)") (class "Default")
      (node (ref "IC3") (pin "6") (pinfunction "P2_6") (pintype "bidirectional"))
      (node (ref "LCD") (pin "13") (pinfunction "13_13") (pintype "passive"))
    )
    (net (code "54") (name "Net-(IC3-P3)") (class "Default")
      (node (ref "IC3") (pin "7") (pinfunction "P3_7") (pintype "bidirectional"))
      (node (ref "LCD") (pin "14") (pinfunction "14_14") (pintype "passive"))
    )
    (net (code "55") (name "Net-(IC3-P4)") (class "Default")
      (node (ref "IC3") (pin "9") (pinfunction "P4_9") (pintype "bidirectional"))
      (node (ref "LCD") (pin "4") (pinfunction "4_4") (pintype "passive"))
    )
    (net (code "56") (name "Net-(IC3-P5)") (class "Default")
      (node (ref "IC3") (pin "10") (pinfunction "P5_10") (pintype "bidirectional"))
      (node (ref "LCD") (pin "5") (pinfunction "5_5") (pintype "passive"))
    )
    (net (code "57") (name "Net-(IC3-P6)") (class "Default")
      (node (ref "IC3") (pin "11") (pinfunction "P6_11") (pintype "bidirectional"))
      (node (ref "LCD") (pin "6") (pinfunction "6_6") (pintype "passive"))
    )
    (net (code "58") (name "Net-(IC3-P7)") (class "Default")
      (node (ref "IC3") (pin "12") (pinfunction "P7_12") (pintype "bidirectional"))
      (node (ref "R14") (pin "1") (pinfunction "1_1") (pintype "passive"))
    )
    (net (code "59") (name "Net-(IC4-LED0)") (class "Default")
      (node (ref "IC4") (pin "6") (pinfunction "LED0_6") (pintype "bidirectional"))
      (node (ref "IC6") (pin "1") (pinfunction "I1_1") (pintype "bidirectional"))
    )
    (net (code "60") (name "Net-(IC4-LED1)") (class "Default")
      (node (ref "IC4") (pin "7") (pinfunction "LED1_7") (pintype "bidirectional"))
      (node (ref "IC6") (pin "2") (pinfunction "I2_2") (pintype "bidirectional"))
    )
    (net (code "61") (name "Net-(IC4-LED2)") (class "Default")
      (node (ref "IC4") (pin "8") (pinfunction "LED2_8") (pintype "bidirectional"))
      (node (ref "IC6") (pin "3") (pinfunction "I3_3") (pintype "bidirectional"))
    )
    (net (code "62") (name "Net-(IC4-LED3)") (class "Default")
      (node (ref "IC4") (pin "9") (pinfunction "LED3_9") (pintype "bidirectional"))
      (node (ref "IC6") (pin "4") (pinfunction "I4_4") (pintype "bidirectional"))
    )
    (net (code "63") (name "Net-(IC4-LED4)") (class "Default")
      (node (ref "IC4") (pin "10") (pinfunction "LED4_10") (pintype "bidirectional"))
      (node (ref "IC6") (pin "5") (pinfunction "I5_5") (pintype "bidirectional"))
    )
    (net (code "64") (name "Net-(IC4-LED5)") (class "Default")
      (node (ref "IC4") (pin "11") (pinfunction "LED5_11") (pintype "bidirectional"))
      (node (ref "IC6") (pin "6") (pinfunction "I6_6") (pintype "bidirectional"))
    )
    (net (code "65") (name "Net-(IC4-LED6)") (class "Default")
      (node (ref "IC4") (pin "12") (pinfunction "LED6_12") (pintype "bidirectional"))
      (node (ref "IC6") (pin "7") (pinfunction "I7_7") (pintype "bidirectional"))
    )
    (net (code "66") (name "Net-(IC4-LED7)") (class "Default")
      (node (ref "IC4") (pin "13") (pinfunction "LED7_13") (pintype "bidirectional"))
      (node (ref "IC6") (pin "8") (pinfunction "I8_8") (pintype "bidirectional"))
    )
    (net (code "67") (name "Net-(IC4-LED8)") (class "Default")
      (node (ref "IC4") (pin "15") (pinfunction "LED8_15") (pintype "bidirectional"))
      (node (ref "IC5") (pin "1") (pinfunction "I1_1") (pintype "bidirectional"))
    )
    (net (code "68") (name "Net-(IC4-LED9)") (class "Default")
      (node (ref "IC4") (pin "16") (pinfunction "LED9_16") (pintype "bidirectional"))
      (node (ref "IC5") (pin "2") (pinfunction "I2_2") (pintype "bidirectional"))
    )
    (net (code "69") (name "Net-(IC4-LED10)") (class "Default")
      (node (ref "IC4") (pin "17") (pinfunction "LED10_17") (pintype "bidirectional"))
      (node (ref "IC5") (pin "3") (pinfunction "I3_3") (pintype "bidirectional"))
    )
    (net (code "70") (name "Net-(IC4-LED11)") (class "Default")
      (node (ref "IC4") (pin "18") (pinfunction "LED11_18") (pintype "bidirectional"))
      (node (ref "IC5") (pin "4") (pinfunction "I4_4") (pintype "bidirectional"))
    )
    (net (code "71") (name "Net-(IC4-LED12)") (class "Default")
      (node (ref "IC4") (pin "19") (pinfunction "LED12_19") (pintype "bidirectional"))
      (node (ref "IC5") (pin "5") (pinfunction "I5_5") (pintype "bidirectional"))
    )
    (net (code "72") (name "Net-(IC4-LED13)") (class "Default")
      (node (ref "IC4") (pin "20") (pinfunction "LED13_20") (pintype "bidirectional"))
      (node (ref "IC5") (pin "6") (pinfunction "I6_6") (pintype "bidirectional"))
    )
    (net (code "73") (name "Net-(IC4-LED14)") (class "Default")
      (node (ref "IC4") (pin "21") (pinfunction "LED14_21") (pintype "bidirectional"))
      (node (ref "IC5") (pin "7") (pinfunction "I7_7") (pintype "bidirectional"))
    )
    (net (code "74") (name "Net-(IC4-LED15)") (class "Default")
      (node (ref "IC4") (pin "22") (pinfunction "LED15_22") (pintype "bidirectional"))
      (node (ref "IC5") (pin "8") (pinfunction "I8_8") (pintype "bidirectional"))
    )
    (net (code "75") (name "Net-(IC5-O1)") (class "Default")
      (node (ref "IC5") (pin "18") (pinfunction "O1_18") (pintype "bidirectional"))
      (node (ref "PWM2") (pin "1") (pinfunction "S_1") (pintype "passive"))
    )
    (net (code "76") (name "Net-(IC5-O2)") (class "Default")
      (node (ref "IC5") (pin "17") (pinfunction "O2_17") (pintype "bidirectional"))
      (node (ref "PWM2") (pin "2") (pinfunction "S_2") (pintype "passive"))
    )
    (net (code "77") (name "Net-(IC5-O3)") (class "Default")
      (node (ref "IC5") (pin "16") (pinfunction "O3_16") (pintype "bidirectional"))
      (node (ref "PWM2") (pin "3") (pinfunction "S_3") (pintype "passive"))
    )
    (net (code "78") (name "Net-(IC5-O4)") (class "Default")
      (node (ref "IC5") (pin "15") (pinfunction "O4_15") (pintype "bidirectional"))
      (node (ref "PWM2") (pin "4") (pinfunction "S_4") (pintype "passive"))
    )
    (net (code "79") (name "Net-(IC5-O5)") (class "Default")
      (node (ref "IC5") (pin "14") (pinfunction "O5_14") (pintype "bidirectional"))
      (node (ref "PWM2") (pin "5") (pinfunction "S_5") (pintype "passive"))
    )
    (net (code "80") (name "Net-(IC5-O6)") (class "Default")
      (node (ref "IC5") (pin "13") (pinfunction "O6_13") (pintype "bidirectional"))
      (node (ref "PWM2") (pin "6") (pinfunction "S_6") (pintype "passive"))
    )
    (net (code "81") (name "Net-(IC5-O7)") (class "Default")
      (node (ref "IC5") (pin "12") (pinfunction "O7_12") (pintype "bidirectional"))
      (node (ref "PWM2") (pin "7") (pinfunction "S_7") (pintype "passive"))
    )
    (net (code "82") (name "Net-(IC5-O8)") (class "Default")
      (node (ref "IC5") (pin "11") (pinfunction "O8_11") (pintype "bidirectional"))
      (node (ref "PWM2") (pin "8") (pinfunction "S_8") (pintype "passive"))
    )
    (net (code "83") (name "Net-(IC6-O1)") (class "Default")
      (node (ref "IC6") (pin "18") (pinfunction "O1_18") (pintype "bidirectional"))
      (node (ref "PWM1") (pin "1") (pinfunction "S_1") (pintype "passive"))
    )
    (net (code "84") (name "Net-(IC6-O2)") (class "Default")
      (node (ref "IC6") (pin "17") (pinfunction "O2_17") (pintype "bidirectional"))
      (node (ref "PWM1") (pin "2") (pinfunction "S_2") (pintype "passive"))
    )
    (net (code "85") (name "Net-(IC6-O3)") (class "Default")
      (node (ref "IC6") (pin "16") (pinfunction "O3_16") (pintype "bidirectional"))
      (node (ref "PWM1") (pin "3") (pinfunction "S_3") (pintype "passive"))
    )
    (net (code "86") (name "Net-(IC6-O4)") (class "Default")
      (node (ref "IC6") (pin "15") (pinfunction "O4_15") (pintype "bidirectional"))
      (node (ref "PWM1") (pin "4") (pinfunction "S_4") (pintype "passive"))
    )
    (net (code "87") (name "Net-(IC6-O5)") (class "Default")
      (node (ref "IC6") (pin "14") (pinfunction "O5_14") (pintype "bidirectional"))
      (node (ref "PWM1") (pin "5") (pinfunction "S_5") (pintype "passive"))
    )
    (net (code "88") (name "Net-(IC6-O6)") (class "Default")
      (node (ref "IC6") (pin "13") (pinfunction "O6_13") (pintype "bidirectional"))
      (node (ref "PWM1") (pin "6") (pinfunction "S_6") (pintype "passive"))
    )
    (net (code "89") (name "Net-(IC6-O7)") (class "Default")
      (node (ref "IC6") (pin "12") (pinfunction "O7_12") (pintype "bidirectional"))
      (node (ref "PWM1") (pin "7") (pinfunction "S_7") (pintype "passive"))
    )
    (net (code "90") (name "Net-(IC6-O8)") (class "Default")
      (node (ref "IC6") (pin "11") (pinfunction "O8_11") (pintype "bidirectional"))
      (node (ref "PWM1") (pin "8") (pinfunction "S_8") (pintype "passive"))
    )
    (net (code "91") (name "Net-(IC8-ANT)") (class "Default")
      (node (ref "ANT") (pin "1") (pinfunction "1_1") (pintype "passive"))
      (node (ref "IC8") (pin "8") (pinfunction "ANT_8") (pintype "bidirectional"))
    )
    (net (code "92") (name "Net-(IC8-FSK{slash}DATA{slash}NFFS)") (class "Default")
      (node (ref "IC8") (pin "3") (pinfunction "FSK/DATA/NFFS_3") (pintype "bidirectional"))
      (node (ref "R10") (pin "2") (pinfunction "2_2") (pintype "passive"))
    )
    (net (code "93") (name "Net-(IC11-ANT)") (class "Default")
      (node (ref "ANT1") (pin "1") (pinfunction "1_1") (pintype "passive"))
      (node (ref "IC11") (pin "8") (pinfunction "ANT_8") (pintype "bidirectional"))
    )
    (net (code "94") (name "Net-(IC11-FSK{slash}DATA{slash}NFFS)") (class "Default")
      (node (ref "IC11") (pin "3") (pinfunction "FSK/DATA/NFFS_3") (pintype "bidirectional"))
      (node (ref "JP1") (pin "1") (pinfunction "1_1") (pintype "passive"))
      (node (ref "R23") (pin "2") (pinfunction "2_2") (pintype "passive"))
    )
    (net (code "95") (name "Net-(IC11-NIRQ)") (class "Default")
      (node (ref "IC11") (pin "2") (pinfunction "NIRQ_2") (pintype "output"))
      (node (ref "JP1") (pin "3") (pinfunction "3_3") (pintype "passive"))
    )
    (net (code "96") (name "Net-(IR1A-S)") (class "Default")
      (node (ref "IR1") (pin "1") (pinfunction "S_1") (pintype "passive"))
      (node (ref "R21") (pin "1") (pinfunction "1_1") (pintype "passive"))
    )
    (net (code "97") (name "Net-(IR2A-S)") (class "Default")
      (node (ref "IR2") (pin "1") (pinfunction "S_1") (pintype "passive"))
      (node (ref "R22") (pin "2") (pinfunction "2_2") (pintype "passive"))
    )
    (net (code "98") (name "Net-(LCD-Pad3)") (class "Default")
      (node (ref "LCD") (pin "3") (pinfunction "3_3") (pintype "passive"))
      (node (ref "R16") (pin "S") (pinfunction "S_S") (pintype "passive"))
    )
    (net (code "99") (name "Net-(LCD-Pad15)") (class "Default")
      (node (ref "LCD") (pin "15") (pinfunction "15_15") (pintype "passive"))
      (node (ref "R15") (pin "2") (pinfunction "2_2") (pintype "passive"))
    )
    (net (code "100") (name "Net-(LEDB-S)") (class "Default")
      (node (ref "LED") (pin "2") (pinfunction "S_2") (pintype "passive"))
      (node (ref "R18") (pin "2") (pinfunction "2_2") (pintype "passive"))
    )
    (net (code "101") (name "Net-(T1-B)") (class "Default")
      (node (ref "R20") (pin "1") (pinfunction "1_1") (pintype "passive"))
      (node (ref "T1") (pin "2") (pinfunction "B_2") (pintype "passive"))
    )
    (net (code "102") (name "Net-(T1-C)") (class "Default")
      (node (ref "R21") (pin "2") (pinfunction "2_2") (pintype "passive"))
      (node (ref "R22") (pin "1") (pinfunction "1_1") (pintype "passive"))
      (node (ref "T1") (pin "3") (pinfunction "C_3") (pintype "passive"))
    )
    (net (code "103") (name "Net-(T2-B)") (class "Default")
      (node (ref "R14") (pin "2") (pinfunction "2_2") (pintype "passive"))
      (node (ref "T2") (pin "2") (pinfunction "B_2") (pintype "passive"))
    )
    (net (code "104") (name "Net-(T2-C)") (class "Default")
      (node (ref "R15") (pin "1") (pinfunction "1_1") (pintype "passive"))
      (node (ref "T2") (pin "3") (pinfunction "C_3") (pintype "passive"))
    )
    (net (code "105") (name "Net-(TSOPC-S)") (class "Default")
      (node (ref "C13") (pin "+") (pinfunction "+_+") (pintype "passive"))
      (node (ref "R17") (pin "1") (pinfunction "1_1") (pintype "passive"))
      (node (ref "TSOP") (pin "3") (pinfunction "S_3") (pintype "passive"))
    )
    (net (code "106") (name "Net-(X1-CTT)") (class "Default")
      (node (ref "C1") (pin "1") (pinfunction "1_1") (pintype "passive"))
      (node (ref "L2") (pin "2") (pinfunction "2_2") (pintype "passive"))
      (node (ref "R5") (pin "2") (pinfunction "2_2") (pintype "passive"))
      (node (ref "R6") (pin "2") (pinfunction "2_2") (pintype "passive"))
      (node (ref "X1") (pin "4") (pinfunction "CTT_4") (pintype "passive"))
    )
    (net (code "107") (name "Net-(X1-LC)") (class "Default")
      (node (ref "R1") (pin "2") (pinfunction "2_2") (pintype "passive"))
      (node (ref "X1") (pin "11") (pinfunction "LC_11") (pintype "passive"))
    )
    (net (code "108") (name "Net-(X1-RC)") (class "Default")
      (node (ref "R2") (pin "2") (pinfunction "2_2") (pintype "passive"))
      (node (ref "X1") (pin "10") (pinfunction "RC_10") (pintype "passive"))
    )
    (net (code "109") (name "unconnected-(IC1-(AIN1{slash}OC0)PB3-Pad4)") (class "Default")
      (node (ref "IC1") (pin "4") (pinfunction "(AIN1/OC0)PB3_4") (pintype "bidirectional"))
    )
    (net (code "110") (name "unconnected-(IC1-(T1)PB1-Pad2)") (class "Default")
      (node (ref "IC1") (pin "2") (pinfunction "(T1)PB1_2") (pintype "bidirectional"))
    )
    (net (code "111") (name "unconnected-(IC1-(TDO)PC4-Pad26)") (class "Default")
      (node (ref "IC1") (pin "26") (pinfunction "(TDO)PC4_26") (pintype "bidirectional"))
    )
    (net (code "112") (name "unconnected-(IC1-(TOSC1)PC6-Pad28)") (class "Default")
      (node (ref "IC1") (pin "28") (pinfunction "(TOSC1)PC6_28") (pintype "bidirectional"))
    )
    (net (code "113") (name "unconnected-(IC1-(TOSC2)PC7-Pad29)") (class "Default")
      (node (ref "IC1") (pin "29") (pinfunction "(TOSC2)PC7_29") (pintype "bidirectional"))
    )
    (net (code "114") (name "unconnected-(IC2-CLKOUT-Pad3)") (class "Default")
      (node (ref "IC2") (pin "3") (pinfunction "CLKOUT_3") (pintype "output"))
    )
    (net (code "115") (name "unconnected-(IC2-WOL-Pad5)") (class "Default")
      (node (ref "IC2") (pin "5") (pinfunction "WOL_5") (pintype "output"))
    )
    (net (code "116") (name "unconnected-(IC3-~{INT}-Pad13)") (class "Default")
      (node (ref "IC3") (pin "13") (pinfunction "~{INT}_13") (pintype "output"))
    )
    (net (code "117") (name "unconnected-(IC8-CLK-Pad5)") (class "Default")
      (node (ref "IC8") (pin "5") (pinfunction "CLK_5") (pintype "output"))
    )
    (net (code "118") (name "unconnected-(IC8-DCLK{slash}CFIL{slash}FFIT-Pad4)") (class "Default")
      (node (ref "IC8") (pin "4") (pinfunction "DCLK/CFIL/FFIT_4") (pintype "bidirectional"))
    )
    (net (code "119") (name "unconnected-(IC8-NINT-Pad11)") (class "Default")
      (node (ref "IC8") (pin "11") (pinfunction "NINT_11") (pintype "bidirectional"))
    )
    (net (code "120") (name "unconnected-(IC8-NRES-Pad6)") (class "Default")
      (node (ref "IC8") (pin "6") (pinfunction "NRES_6") (pintype "bidirectional"))
    )
    (net (code "121") (name "unconnected-(IC11-CLK-Pad5)") (class "Default")
      (node (ref "IC11") (pin "5") (pinfunction "CLK_5") (pintype "output"))
    )
    (net (code "122") (name "unconnected-(IC11-DCLK{slash}CFIL{slash}FFIT-Pad4)") (class "Default")
      (node (ref "IC11") (pin "4") (pinfunction "DCLK/CFIL/FFIT_4") (pintype "bidirectional"))
    )
    (net (code "123") (name "unconnected-(IC11-NINT-Pad11)") (class "Default")
      (node (ref "IC11") (pin "11") (pinfunction "NINT_11") (pintype "bidirectional"))
    )
    (net (code "124") (name "unconnected-(IC11-NRES-Pad6)") (class "Default")
      (node (ref "IC11") (pin "6") (pinfunction "NRES_6") (pintype "bidirectional"))
    )
    (net (code "125") (name "unconnected-(X1-CG1-Pad7)") (class "Default")
      (node (ref "X1") (pin "7") (pinfunction "CG1_7") (pintype "passive"))
    )
    (net (code "126") (name "unconnected-(X1-CTR-Pad5)") (class "Default")
      (node (ref "X1") (pin "5") (pinfunction "CTR_5") (pintype "passive"))
    )
  )
)
